# DualBuck.net
KiCad netlist of a schematic drawn in Altium Designer
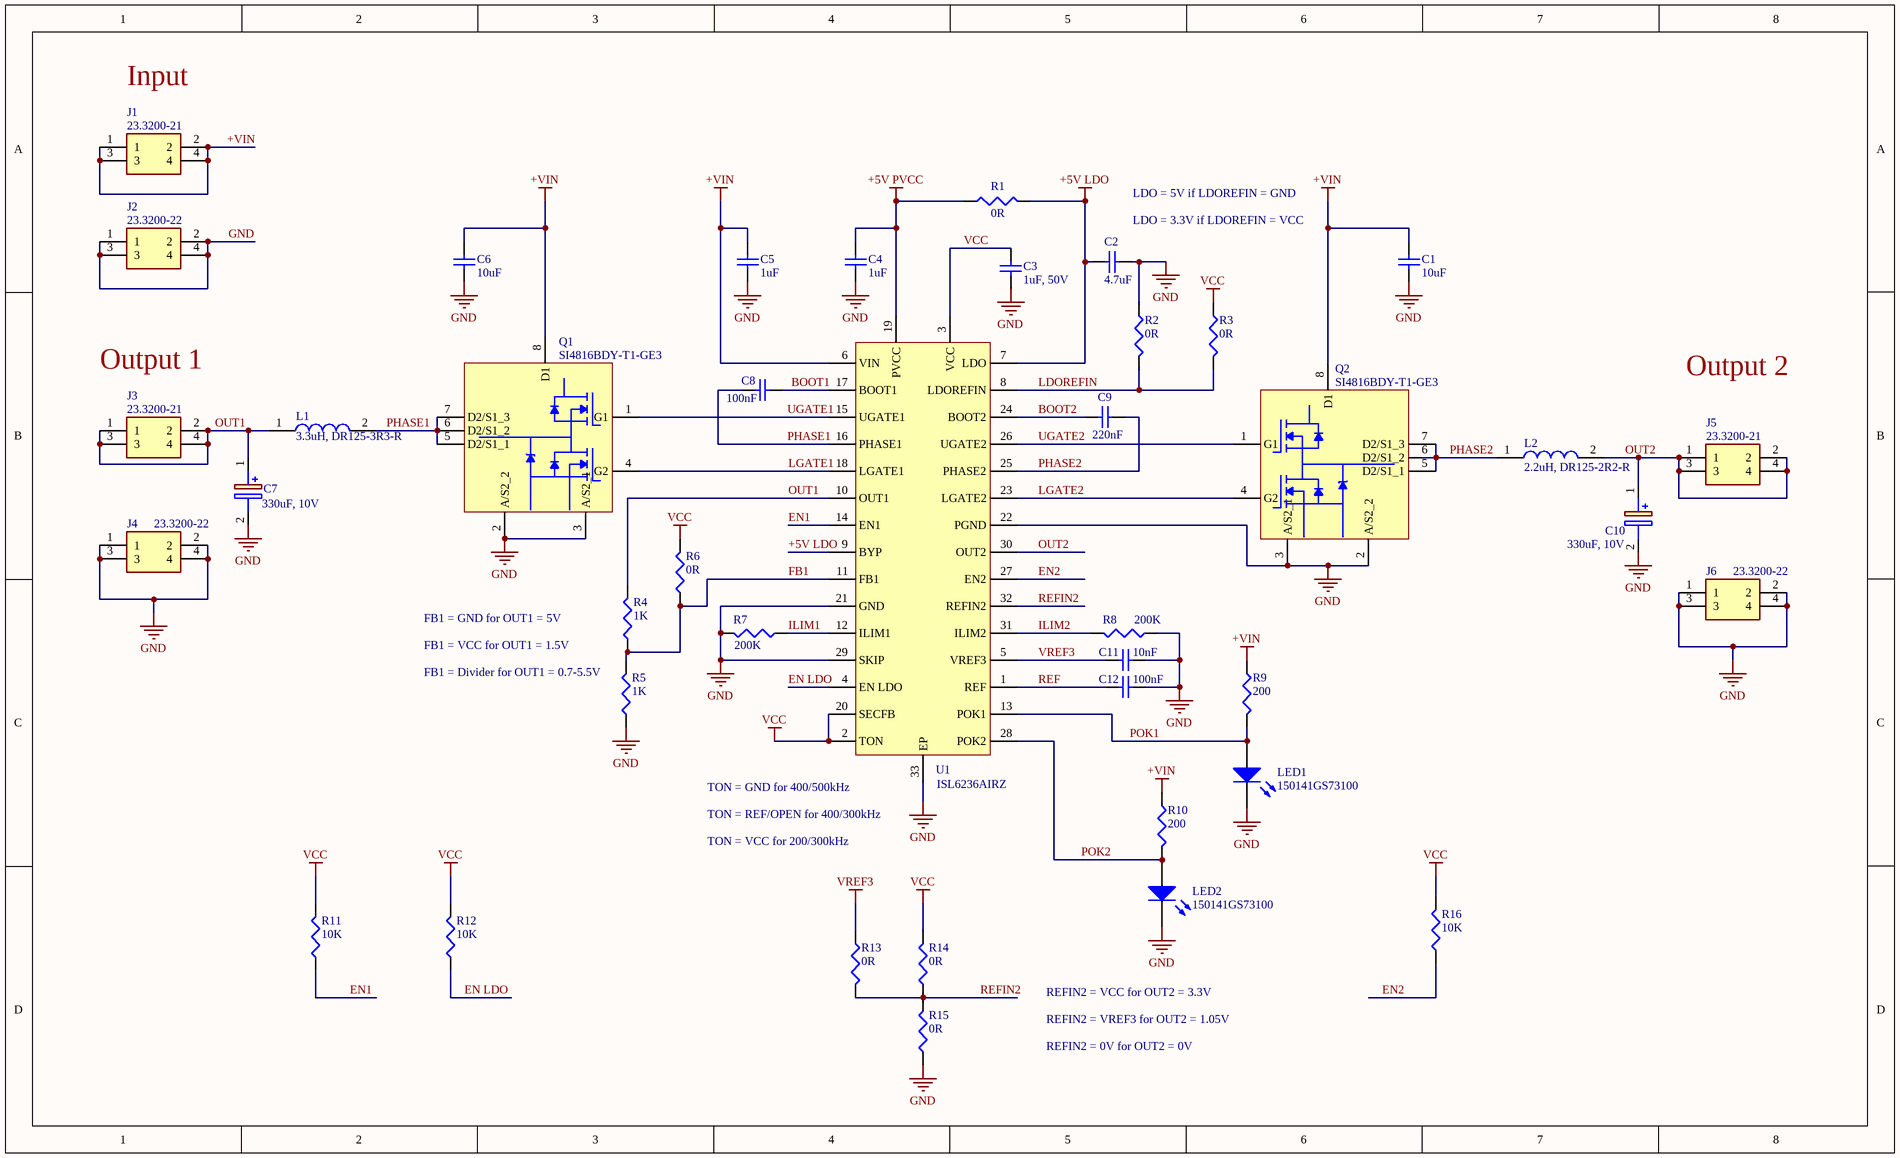
[diagram p0: DualBuck.SchDoc]

(export (version "E")
  (design (tool "Eeschema 10.0.6"))
  (components
    (comp (ref "C1")
      (value "10uF")
      (footprint "C1210")
      (description "Capacitor")
      (fields (field (name "PUBLISHER") "Altium Limited"))
      (libsource (lib "Miscellaneous Devices") (part "Cap"))
    )
    (comp (ref "C2")
      (value "4.7uF")
      (footprint "C1206")
      (description "Capacitor")
      (fields (field (name "PUBLISHER") "Altium Limited"))
      (libsource (lib "Miscellaneous Devices") (part "Cap"))
    )
    (comp (ref "C3")
      (value "1uF, 50V")
      (footprint "C0805")
      (description "Capacitor")
      (fields (field (name "PUBLISHER") "Altium Limited"))
      (libsource (lib "Miscellaneous Devices") (part "Cap"))
    )
    (comp (ref "C4")
      (value "1uF")
      (footprint "C0805")
      (description "Capacitor")
      (fields (field (name "PUBLISHER") "Altium Limited"))
      (libsource (lib "Miscellaneous Devices") (part "Cap"))
    )
    (comp (ref "C5")
      (value "1uF")
      (footprint "C0805")
      (description "Capacitor")
      (fields (field (name "PUBLISHER") "Altium Limited"))
      (libsource (lib "Miscellaneous Devices") (part "Cap"))
    )
    (comp (ref "C6")
      (value "10uF")
      (footprint "C1210")
      (description "Capacitor")
      (fields (field (name "PUBLISHER") "Altium Limited"))
      (libsource (lib "Miscellaneous Devices") (part "Cap"))
    )
    (comp (ref "C7")
      (value "330uF, 10V")
      (footprint "SamacSys:CAPPM7343X430N")
      (description "Capacitor Polarised")
      (fields
        (field (name "MANUFACTURER_PART_NUMBER") "T530X337M010ATE004")
        (field (name "MOUSER PART NUMBER") "80-T530X337M010ATE4")
      )
      (libsource (lib "*") (part "T530X337M010ATE004"))
    )
    (comp (ref "C8")
      (value "100nF")
      (footprint "C0805")
      (description "Capacitor")
      (fields (field (name "PUBLISHER") "Altium Limited"))
      (libsource (lib "Miscellaneous Devices") (part "Cap"))
    )
    (comp (ref "C9")
      (value "220nF")
      (footprint "C0805")
      (description "Capacitor")
      (fields (field (name "PUBLISHER") "Altium Limited"))
      (libsource (lib "Miscellaneous Devices") (part "Cap"))
    )
    (comp (ref "C10")
      (value "330uF, 10V")
      (footprint "SamacSys:CAPPM7343X430N")
      (description "Capacitor Polarised")
      (fields
        (field (name "MANUFACTURER_PART_NUMBER") "T530X337M010ATE004")
        (field (name "MOUSER PART NUMBER") "80-T530X337M010ATE4")
      )
      (libsource (lib "*") (part "T530X337M010ATE004"))
    )
    (comp (ref "C11")
      (value "10nF")
      (footprint "C0805")
      (description "Capacitor")
      (fields (field (name "PUBLISHER") "Altium Limited"))
      (libsource (lib "Miscellaneous Devices") (part "Cap"))
    )
    (comp (ref "C12")
      (value "100nF")
      (footprint "C0805")
      (description "Capacitor")
      (fields (field (name "PUBLISHER") "Altium Limited"))
      (libsource (lib "Miscellaneous Devices") (part "Cap"))
    )
    (comp (ref "J1")
      (value "23.3200-21")
      (footprint "SamacSys:23320021")
      (description "Connector")
      (fields (field (name "RS PART NUMBER") "4225051"))
      (libsource (lib "*") (part "23.3200-21"))
    )
    (comp (ref "J2")
      (value "23.3200-22")
      (footprint "SamacSys:23320022")
      (description "Connector")
      (fields (field (name "RS PART NUMBER") "4225067"))
      (libsource (lib "*") (part "23.3200-22"))
    )
    (comp (ref "J3")
      (value "23.3200-21")
      (footprint "SamacSys:23320021")
      (description "Connector")
      (fields (field (name "RS PART NUMBER") "4225051"))
      (libsource (lib "*") (part "23.3200-21"))
    )
    (comp (ref "J4")
      (value "23.3200-22")
      (footprint "SamacSys:23320022")
      (description "Connector")
      (fields (field (name "RS PART NUMBER") "4225067"))
      (libsource (lib "*") (part "23.3200-22"))
    )
    (comp (ref "J5")
      (value "23.3200-21")
      (footprint "SamacSys:23320021")
      (description "Connector")
      (fields (field (name "RS PART NUMBER") "4225051"))
      (libsource (lib "*") (part "23.3200-21"))
    )
    (comp (ref "J6")
      (value "23.3200-22")
      (footprint "SamacSys:23320022")
      (description "Connector")
      (fields (field (name "RS PART NUMBER") "4225067"))
      (libsource (lib "*") (part "23.3200-22"))
    )
    (comp (ref "L1")
      (value "3.3uH, DR125-3R3-R")
      (footprint "SamacSys:INDPM125125X600N")
      (description "Inductor")
      (fields
        (field (name "MANUFACTURER_PART_NUMBER") "DR125-3R3-R")
        (field (name "RS PART NUMBER") "7700974")
      )
      (libsource (lib "*") (part "DR125-3R3-R"))
    )
    (comp (ref "L2")
      (value "2.2uH, DR125-2R2-R")
      (footprint "SamacSys:INDPM125125X600N")
      (description "Inductor")
      (fields
        (field (name "MANUFACTURER_PART_NUMBER") "DR125-2R2-R")
        (field (name "RS PART NUMBER") "7700968")
      )
      (libsource (lib "*") (part "DR125-2R2-R"))
    )
    (comp (ref "LED1")
      (value "150141GS73100")
      (footprint "3528")
      (description "SMD mono-color Top LED, WL-SMTW, Green")
      (libsource (lib "WL-SMTW SMD TOP LED mono-color waterclear") (part "150141GS73100"))
    )
    (comp (ref "LED2")
      (value "150141GS73100")
      (footprint "3528")
      (description "SMD mono-color Top LED, WL-SMTW, Green")
      (libsource (lib "WL-SMTW SMD TOP LED mono-color waterclear") (part "150141GS73100"))
    )
    (comp (ref "Q1")
      (value "SI4816BDY-T1-GE3")
      (footprint "SamacSys:SOT127P600X175-8N")
      (description "Integrated Circuit")
      (libsource (lib "DualBuck") (part "SI4816BDY-T1-GE3"))
    )
    (comp (ref "Q2")
      (value "SI4816BDY-T1-GE3")
      (footprint "SamacSys:SOT127P600X175-8N")
      (description "Integrated Circuit")
      (libsource (lib "") (part "SI4816BDY-T1-GE3_1"))
    )
    (comp (ref "R1")
      (value "0R")
      (footprint "PcbLib:R0805")
      (description "Resistor")
      (fields (field (name "Comment") "Res3") (field (name "PUBLISHER") "Altium Limited"))
      (libsource (lib "Miscellaneous Devices") (part "Res3"))
    )
    (comp (ref "R2")
      (value "0R")
      (footprint "PcbLib:R0805")
      (description "Resistor")
      (fields (field (name "Comment") "Res3") (field (name "PUBLISHER") "Altium Limited"))
      (libsource (lib "Miscellaneous Devices") (part "Res3"))
    )
    (comp (ref "R3")
      (value "0R")
      (footprint "PcbLib:R0805")
      (description "Resistor")
      (fields (field (name "Comment") "Res3") (field (name "PUBLISHER") "Altium Limited"))
      (libsource (lib "Miscellaneous Devices") (part "Res3"))
    )
    (comp (ref "R4")
      (value "1K")
      (footprint "PcbLib:R0805")
      (description "Resistor")
      (fields (field (name "Comment") "Res3") (field (name "PUBLISHER") "Altium Limited"))
      (libsource (lib "Miscellaneous Devices") (part "Res3"))
    )
    (comp (ref "R5")
      (value "1K")
      (footprint "PcbLib:R0805")
      (description "Resistor")
      (fields (field (name "Comment") "Res3") (field (name "PUBLISHER") "Altium Limited"))
      (libsource (lib "Miscellaneous Devices") (part "Res3"))
    )
    (comp (ref "R6")
      (value "0R")
      (footprint "PcbLib:R0805")
      (description "Resistor")
      (fields (field (name "Comment") "Res3") (field (name "PUBLISHER") "Altium Limited"))
      (libsource (lib "Miscellaneous Devices") (part "Res3"))
    )
    (comp (ref "R7")
      (value "200K")
      (footprint "PcbLib:R0805")
      (description "Resistor")
      (fields (field (name "Comment") "Res3") (field (name "PUBLISHER") "Altium Limited"))
      (libsource (lib "Miscellaneous Devices") (part "Res3"))
    )
    (comp (ref "R8")
      (value "200K")
      (footprint "PcbLib:R0805")
      (description "Resistor")
      (fields (field (name "Comment") "Res3") (field (name "PUBLISHER") "Altium Limited"))
      (libsource (lib "Miscellaneous Devices") (part "Res3"))
    )
    (comp (ref "R9")
      (value "200")
      (footprint "PcbLib:R0805")
      (description "Resistor")
      (fields (field (name "Comment") "Res3") (field (name "PUBLISHER") "Altium Limited"))
      (libsource (lib "Miscellaneous Devices") (part "Res3"))
    )
    (comp (ref "R10")
      (value "200")
      (footprint "PcbLib:R0805")
      (description "Resistor")
      (fields (field (name "Comment") "Res3") (field (name "PUBLISHER") "Altium Limited"))
      (libsource (lib "Miscellaneous Devices") (part "Res3"))
    )
    (comp (ref "R11")
      (value "10K")
      (footprint "PcbLib:R0805")
      (description "Resistor")
      (fields (field (name "PUBLISHER") "Altium Limited"))
      (libsource (lib "Miscellaneous Devices") (part "Res3"))
    )
    (comp (ref "R12")
      (value "10K")
      (footprint "PcbLib:R0805")
      (description "Resistor")
      (fields (field (name "Comment") "Res3") (field (name "PUBLISHER") "Altium Limited"))
      (libsource (lib "Miscellaneous Devices") (part "Res3"))
    )
    (comp (ref "R13")
      (value "0R")
      (footprint "PcbLib:R0805")
      (description "Resistor")
      (fields (field (name "Comment") "Res3") (field (name "PUBLISHER") "Altium Limited"))
      (libsource (lib "Miscellaneous Devices") (part "Res3"))
    )
    (comp (ref "R14")
      (value "0R")
      (footprint "PcbLib:R0805")
      (description "Resistor")
      (fields (field (name "Comment") "Res3") (field (name "PUBLISHER") "Altium Limited"))
      (libsource (lib "Miscellaneous Devices") (part "Res3"))
    )
    (comp (ref "R15")
      (value "0R")
      (footprint "PcbLib:R0805")
      (description "Resistor")
      (fields (field (name "Comment") "Res3") (field (name "PUBLISHER") "Altium Limited"))
      (libsource (lib "Miscellaneous Devices") (part "Res3"))
    )
    (comp (ref "R16")
      (value "10K")
      (footprint "PcbLib:R0805")
      (description "Resistor")
      (fields (field (name "Comment") "Res3") (field (name "PUBLISHER") "Altium Limited"))
      (libsource (lib "Miscellaneous Devices") (part "Res3"))
    )
    (comp (ref "U1")
      (value "ISL6236AIRZ")
      (footprint "QFN50P500X500X100-33N")
      (description "Integrated Circuit")
      (libsource (lib "DualBuck") (part "ISL6236AIRZ"))
    )
  )
  (nets
    (net (code "1") (name "+5V LDO") (class "Default")
      (node (ref "C2") (pin "2") (pinfunction "2_2") (pintype "passive"))
      (node (ref "R1") (pin "2") (pinfunction "2_2") (pintype "passive"))
      (node (ref "U1") (pin "7") (pinfunction "LDO_7") (pintype "passive"))
      (node (ref "U1") (pin "9") (pinfunction "BYP_9") (pintype "passive"))
    )
    (net (code "2") (name "+5V PVCC") (class "Default")
      (node (ref "C4") (pin "2") (pinfunction "2_2") (pintype "passive"))
      (node (ref "R1") (pin "1") (pinfunction "1_1") (pintype "passive"))
      (node (ref "U1") (pin "19") (pinfunction "PVCC_19") (pintype "passive"))
    )
    (net (code "3") (name "+VIN") (class "Default")
      (node (ref "C1") (pin "2") (pinfunction "2_2") (pintype "passive"))
      (node (ref "C5") (pin "2") (pinfunction "2_2") (pintype "passive"))
      (node (ref "C6") (pin "2") (pinfunction "2_2") (pintype "passive"))
      (node (ref "J1") (pin "1") (pinfunction "1_1") (pintype "passive"))
      (node (ref "J1") (pin "2") (pinfunction "2_2") (pintype "passive"))
      (node (ref "J1") (pin "3") (pinfunction "3_3") (pintype "passive"))
      (node (ref "J1") (pin "4") (pinfunction "4_4") (pintype "passive"))
      (node (ref "Q1") (pin "8") (pinfunction "D1_8") (pintype "passive"))
      (node (ref "Q2") (pin "8") (pinfunction "D1_8") (pintype "passive"))
      (node (ref "R10") (pin "1") (pinfunction "1_1") (pintype "passive"))
      (node (ref "R9") (pin "1") (pinfunction "1_1") (pintype "passive"))
      (node (ref "U1") (pin "6") (pinfunction "VIN_6") (pintype "passive"))
    )
    (net (code "4") (name "/BOOT1") (class "Default")
      (node (ref "C8") (pin "1") (pinfunction "1_1") (pintype "passive"))
      (node (ref "U1") (pin "17") (pinfunction "BOOT1_17") (pintype "passive"))
    )
    (net (code "5") (name "/BOOT2") (class "Default")
      (node (ref "C9") (pin "2") (pinfunction "2_2") (pintype "passive"))
      (node (ref "U1") (pin "24") (pinfunction "BOOT2_24") (pintype "passive"))
    )
    (net (code "6") (name "/EN LDO") (class "Default")
      (node (ref "R12") (pin "1") (pinfunction "1_1") (pintype "passive"))
      (node (ref "U1") (pin "4") (pinfunction "EN_LDO_4") (pintype "passive"))
    )
    (net (code "7") (name "/EN1") (class "Default")
      (node (ref "R11") (pin "1") (pinfunction "1_1") (pintype "passive"))
      (node (ref "U1") (pin "14") (pinfunction "EN1_14") (pintype "passive"))
    )
    (net (code "8") (name "/EN2") (class "Default")
      (node (ref "R16") (pin "1") (pinfunction "1_1") (pintype "passive"))
      (node (ref "U1") (pin "27") (pinfunction "EN2_27") (pintype "passive"))
    )
    (net (code "9") (name "/FB1") (class "Default")
      (node (ref "R4") (pin "1") (pinfunction "1_1") (pintype "passive"))
      (node (ref "R5") (pin "2") (pinfunction "2_2") (pintype "passive"))
      (node (ref "R6") (pin "1") (pinfunction "1_1") (pintype "passive"))
      (node (ref "U1") (pin "11") (pinfunction "FB1_11") (pintype "passive"))
    )
    (net (code "10") (name "/ILIM1") (class "Default")
      (node (ref "R7") (pin "1") (pinfunction "1_1") (pintype "passive"))
      (node (ref "U1") (pin "12") (pinfunction "ILIM1_12") (pintype "passive"))
    )
    (net (code "11") (name "/ILIM2") (class "Default")
      (node (ref "R8") (pin "2") (pinfunction "2_2") (pintype "passive"))
      (node (ref "U1") (pin "31") (pinfunction "ILIM2_31") (pintype "passive"))
    )
    (net (code "12") (name "/LDOREFIN") (class "Default")
      (node (ref "R2") (pin "2") (pinfunction "2_2") (pintype "passive"))
      (node (ref "R3") (pin "2") (pinfunction "2_2") (pintype "passive"))
      (node (ref "U1") (pin "8") (pinfunction "LDOREFIN_8") (pintype "passive"))
    )
    (net (code "13") (name "/LGATE1") (class "Default")
      (node (ref "Q1") (pin "4") (pinfunction "G2_4") (pintype "passive"))
      (node (ref "U1") (pin "18") (pinfunction "LGATE1_18") (pintype "passive"))
    )
    (net (code "14") (name "/LGATE2") (class "Default")
      (node (ref "Q2") (pin "4") (pinfunction "G2_4") (pintype "passive"))
      (node (ref "U1") (pin "23") (pinfunction "LGATE2_23") (pintype "passive"))
    )
    (net (code "15") (name "/OUT1") (class "Default")
      (node (ref "C7") (pin "1") (pinfunction "+_1") (pintype "passive"))
      (node (ref "J3") (pin "1") (pinfunction "1_1") (pintype "passive"))
      (node (ref "J3") (pin "2") (pinfunction "2_2") (pintype "passive"))
      (node (ref "J3") (pin "3") (pinfunction "3_3") (pintype "passive"))
      (node (ref "J3") (pin "4") (pinfunction "4_4") (pintype "passive"))
      (node (ref "L1") (pin "1") (pinfunction "1_1") (pintype "passive"))
      (node (ref "R4") (pin "2") (pinfunction "2_2") (pintype "passive"))
      (node (ref "U1") (pin "10") (pinfunction "OUT1_10") (pintype "passive"))
    )
    (net (code "16") (name "/OUT2") (class "Default")
      (node (ref "C10") (pin "1") (pinfunction "+_1") (pintype "passive"))
      (node (ref "J5") (pin "1") (pinfunction "1_1") (pintype "passive"))
      (node (ref "J5") (pin "2") (pinfunction "2_2") (pintype "passive"))
      (node (ref "J5") (pin "3") (pinfunction "3_3") (pintype "passive"))
      (node (ref "J5") (pin "4") (pinfunction "4_4") (pintype "passive"))
      (node (ref "L2") (pin "2") (pinfunction "2_2") (pintype "passive"))
      (node (ref "U1") (pin "30") (pinfunction "OUT2_30") (pintype "passive"))
    )
    (net (code "17") (name "/PHASE1") (class "Default")
      (node (ref "C8") (pin "2") (pinfunction "2_2") (pintype "passive"))
      (node (ref "L1") (pin "2") (pinfunction "2_2") (pintype "passive"))
      (node (ref "Q1") (pin "5") (pinfunction "D2/S1_1_5") (pintype "passive"))
      (node (ref "Q1") (pin "6") (pinfunction "D2/S1_2_6") (pintype "passive"))
      (node (ref "Q1") (pin "7") (pinfunction "D2/S1_3_7") (pintype "passive"))
      (node (ref "U1") (pin "16") (pinfunction "PHASE1_16") (pintype "passive"))
    )
    (net (code "18") (name "/PHASE2") (class "Default")
      (node (ref "C9") (pin "1") (pinfunction "1_1") (pintype "passive"))
      (node (ref "L2") (pin "1") (pinfunction "1_1") (pintype "passive"))
      (node (ref "Q2") (pin "5") (pinfunction "D2/S1_1_5") (pintype "passive"))
      (node (ref "Q2") (pin "6") (pinfunction "D2/S1_2_6") (pintype "passive"))
      (node (ref "Q2") (pin "7") (pinfunction "D2/S1_3_7") (pintype "passive"))
      (node (ref "U1") (pin "25") (pinfunction "PHASE2_25") (pintype "passive"))
    )
    (net (code "19") (name "/POK1") (class "Default")
      (node (ref "LED1") (pin "2") (pinfunction "A_2") (pintype "passive"))
      (node (ref "R9") (pin "2") (pinfunction "2_2") (pintype "passive"))
      (node (ref "U1") (pin "13") (pinfunction "POK1_13") (pintype "passive"))
    )
    (net (code "20") (name "/POK2") (class "Default")
      (node (ref "LED2") (pin "2") (pinfunction "A_2") (pintype "passive"))
      (node (ref "R10") (pin "2") (pinfunction "2_2") (pintype "passive"))
      (node (ref "U1") (pin "28") (pinfunction "POK2_28") (pintype "passive"))
    )
    (net (code "21") (name "/REF") (class "Default")
      (node (ref "C12") (pin "2") (pinfunction "2_2") (pintype "passive"))
      (node (ref "U1") (pin "1") (pinfunction "REF_1") (pintype "passive"))
    )
    (net (code "22") (name "/REFIN2") (class "Default")
      (node (ref "R13") (pin "2") (pinfunction "2_2") (pintype "passive"))
      (node (ref "R14") (pin "2") (pinfunction "2_2") (pintype "passive"))
      (node (ref "R15") (pin "1") (pinfunction "1_1") (pintype "passive"))
      (node (ref "U1") (pin "32") (pinfunction "REFIN2_32") (pintype "passive"))
    )
    (net (code "23") (name "/UGATE1") (class "Default")
      (node (ref "Q1") (pin "1") (pinfunction "G1_1") (pintype "passive"))
      (node (ref "U1") (pin "15") (pinfunction "UGATE1_15") (pintype "passive"))
    )
    (net (code "24") (name "/UGATE2") (class "Default")
      (node (ref "Q2") (pin "1") (pinfunction "G1_1") (pintype "passive"))
      (node (ref "U1") (pin "26") (pinfunction "UGATE2_26") (pintype "passive"))
    )
    (net (code "25") (name "GND") (class "Default")
      (node (ref "C1") (pin "1") (pinfunction "1_1") (pintype "passive"))
      (node (ref "C10") (pin "2") (pinfunction "-_2") (pintype "passive"))
      (node (ref "C11") (pin "1") (pinfunction "1_1") (pintype "passive"))
      (node (ref "C12") (pin "1") (pinfunction "1_1") (pintype "passive"))
      (node (ref "C2") (pin "1") (pinfunction "1_1") (pintype "passive"))
      (node (ref "C3") (pin "1") (pinfunction "1_1") (pintype "passive"))
      (node (ref "C4") (pin "1") (pinfunction "1_1") (pintype "passive"))
      (node (ref "C5") (pin "1") (pinfunction "1_1") (pintype "passive"))
      (node (ref "C6") (pin "1") (pinfunction "1_1") (pintype "passive"))
      (node (ref "C7") (pin "2") (pinfunction "-_2") (pintype "passive"))
      (node (ref "J2") (pin "1") (pinfunction "1_1") (pintype "passive"))
      (node (ref "J2") (pin "2") (pinfunction "2_2") (pintype "passive"))
      (node (ref "J2") (pin "3") (pinfunction "3_3") (pintype "passive"))
      (node (ref "J2") (pin "4") (pinfunction "4_4") (pintype "passive"))
      (node (ref "J4") (pin "1") (pinfunction "1_1") (pintype "passive"))
      (node (ref "J4") (pin "2") (pinfunction "2_2") (pintype "passive"))
      (node (ref "J4") (pin "3") (pinfunction "3_3") (pintype "passive"))
      (node (ref "J4") (pin "4") (pinfunction "4_4") (pintype "passive"))
      (node (ref "J6") (pin "1") (pinfunction "1_1") (pintype "passive"))
      (node (ref "J6") (pin "2") (pinfunction "2_2") (pintype "passive"))
      (node (ref "J6") (pin "3") (pinfunction "3_3") (pintype "passive"))
      (node (ref "J6") (pin "4") (pinfunction "4_4") (pintype "passive"))
      (node (ref "LED1") (pin "1") (pinfunction "K_1") (pintype "passive"))
      (node (ref "LED2") (pin "1") (pinfunction "K_1") (pintype "passive"))
      (node (ref "Q1") (pin "2") (pinfunction "A/S2_2_2") (pintype "passive"))
      (node (ref "Q1") (pin "3") (pinfunction "A/S2_1_3") (pintype "passive"))
      (node (ref "Q2") (pin "2") (pinfunction "A/S2_2_2") (pintype "passive"))
      (node (ref "Q2") (pin "3") (pinfunction "A/S2_1_3") (pintype "passive"))
      (node (ref "R15") (pin "2") (pinfunction "2_2") (pintype "passive"))
      (node (ref "R2") (pin "1") (pinfunction "1_1") (pintype "passive"))
      (node (ref "R5") (pin "1") (pinfunction "1_1") (pintype "passive"))
      (node (ref "R7") (pin "2") (pinfunction "2_2") (pintype "passive"))
      (node (ref "R8") (pin "1") (pinfunction "1_1") (pintype "passive"))
      (node (ref "U1") (pin "21") (pinfunction "GND_21") (pintype "passive"))
      (node (ref "U1") (pin "22") (pinfunction "PGND_22") (pintype "power_in"))
      (node (ref "U1") (pin "29") (pinfunction "SKIP_29") (pintype "passive"))
      (node (ref "U1") (pin "33") (pinfunction "EP_33") (pintype "passive"))
    )
    (net (code "26") (name "VCC") (class "Default")
      (node (ref "C3") (pin "2") (pinfunction "2_2") (pintype "passive"))
      (node (ref "R11") (pin "2") (pinfunction "2_2") (pintype "passive"))
      (node (ref "R12") (pin "2") (pinfunction "2_2") (pintype "passive"))
      (node (ref "R14") (pin "1") (pinfunction "1_1") (pintype "passive"))
      (node (ref "R16") (pin "2") (pinfunction "2_2") (pintype "passive"))
      (node (ref "R3") (pin "1") (pinfunction "1_1") (pintype "passive"))
      (node (ref "R6") (pin "2") (pinfunction "2_2") (pintype "passive"))
      (node (ref "U1") (pin "2") (pinfunction "TON_2") (pintype "passive"))
      (node (ref "U1") (pin "20") (pinfunction "SECFB_20") (pintype "passive"))
      (node (ref "U1") (pin "3") (pinfunction "VCC_3") (pintype "passive"))
    )
    (net (code "27") (name "VREF3") (class "Default")
      (node (ref "C11") (pin "2") (pinfunction "2_2") (pintype "passive"))
      (node (ref "R13") (pin "1") (pinfunction "1_1") (pintype "passive"))
      (node (ref "U1") (pin "5") (pinfunction "VREF3_5") (pintype "passive"))
    )
  )
)
